# dsau-micro-zed-bank35.net
KiCad netlist of a schematic drawn in Altium Designer
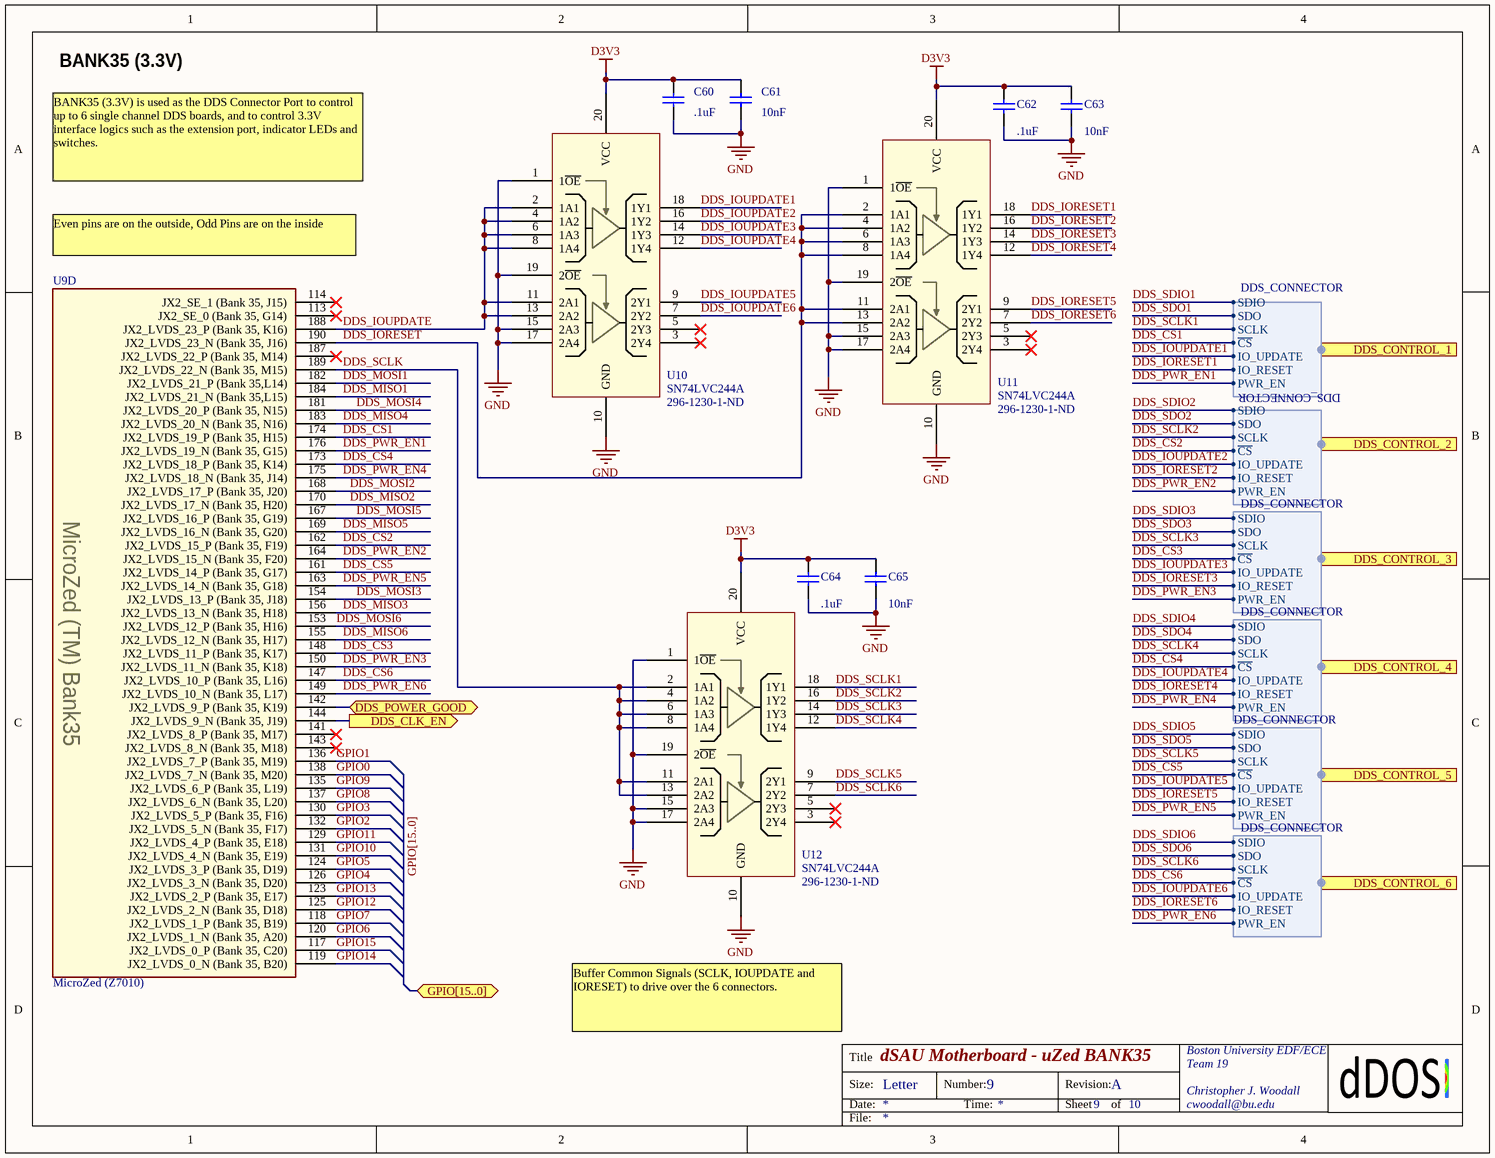
[diagram p0: dsau-micro-zed-bank35.SchDoc]

(export (version "E")
  (design (tool "Eeschema 10.0.6"))
  (components
    (comp (ref "C60")
      (value ".1uF")
      (footprint "CAPC1608L")
      (description "Capacitor")
      (fields
        (field (name "MANUFACTURER") "Yageo")
        (field (name "MANUFACTURER PART NUMBER") "CC0603ZRY5V9BB104")
        (field (name "PUBLISHER") "Altium Limited")
      )
      (libsource (lib "Miscellaneous Devices") (part "Cap"))
    )
    (comp (ref "C61")
      (value "10nF")
      (footprint "CAPC1608L")
      (description "Capacitor")
      (fields
        (field (name "MANUFACTURER") "Kemet")
        (field (name "MANUFACTURER PART NUMBER") "C0603C103K3GACTU")
        (field (name "PUBLISHER") "Altium Limited")
      )
      (libsource (lib "Miscellaneous Devices") (part "Cap"))
    )
    (comp (ref "C62")
      (value ".1uF")
      (footprint "CAPC1608L")
      (description "Capacitor")
      (fields
        (field (name "MANUFACTURER") "Yageo")
        (field (name "MANUFACTURER PART NUMBER") "CC0603ZRY5V9BB104")
        (field (name "PUBLISHER") "Altium Limited")
      )
      (libsource (lib "Miscellaneous Devices") (part "Cap"))
    )
    (comp (ref "C63")
      (value "10nF")
      (footprint "CAPC1608L")
      (description "Capacitor")
      (fields
        (field (name "MANUFACTURER") "Kemet")
        (field (name "MANUFACTURER PART NUMBER") "C0603C103K3GACTU")
        (field (name "PUBLISHER") "Altium Limited")
      )
      (libsource (lib "Miscellaneous Devices") (part "Cap"))
    )
    (comp (ref "C64")
      (value ".1uF")
      (footprint "CAPC1608L")
      (description "Capacitor")
      (fields
        (field (name "MANUFACTURER") "Yageo")
        (field (name "MANUFACTURER PART NUMBER") "CC0603ZRY5V9BB104")
        (field (name "PUBLISHER") "Altium Limited")
      )
      (libsource (lib "Miscellaneous Devices") (part "Cap"))
    )
    (comp (ref "C65")
      (value "10nF")
      (footprint "CAPC1608L")
      (description "Capacitor")
      (fields
        (field (name "MANUFACTURER") "Kemet")
        (field (name "MANUFACTURER PART NUMBER") "C0603C103K3GACTU")
        (field (name "PUBLISHER") "Altium Limited")
      )
      (libsource (lib "Miscellaneous Devices") (part "Cap"))
    )
    (comp (ref "U9")
      (value "MicroZed (Z7010)")
      (footprint "MicroZed_MatingSide")
      (fields
        (field (name "MANUFACTURER") "Avnet")
        (field (name "MANFACTURER PART NUMBER") "AES-Z7MB-7Z010-G")
      )
      (libsource (lib "dsau-motherboard") (part "MicroZed"))
    )
    (comp (ref "U10")
      (value "SN74LVC244A")
      (footprint "TSOP64P640X120-20N")
      (fields
        (field (name "MANUFACTURER") "Texas Instruments")
        (field (name "SUPPLIER PART NUMBER 1") "296-1230-1-ND")
      )
      (libsource (lib "dsau-motherboard") (part "SN74LVC244A"))
    )
    (comp (ref "U11")
      (value "SN74LVC244A")
      (footprint "TSOP64P640X120-20N")
      (fields
        (field (name "MANUFACTURER") "Texas Instruments")
        (field (name "SUPPLIER PART NUMBER 1") "296-1230-1-ND")
      )
      (libsource (lib "dsau-motherboard") (part "SN74LVC244A"))
    )
    (comp (ref "U12")
      (value "SN74LVC244A")
      (footprint "TSOP64P640X120-20N")
      (fields
        (field (name "MANUFACTURER") "Texas Instruments")
        (field (name "SUPPLIER PART NUMBER 1") "296-1230-1-ND")
      )
      (libsource (lib "dsau-motherboard") (part "SN74LVC244A"))
    )
  )
  (nets
    (net (code "3") (name "/DDS_CLK_EN") (class "Default")
      (node (ref "U9") (pin "144") (pinfunction "JX2_LVDS_9_N_(Bank_35,_J19)_144") (pintype "passive"))
    )
    (net (code "5") (name "/DDS_CS1") (class "Default")
      (node (ref "U9") (pin "174") (pinfunction "JX2_LVDS_19_P_(Bank_35,_H15)_174") (pintype "passive"))
    )
    (net (code "6") (name "/DDS_CS2") (class "Default")
      (node (ref "U9") (pin "162") (pinfunction "JX2_LVDS_15_P_(Bank_35,_F19)_162") (pintype "passive"))
    )
    (net (code "7") (name "/DDS_CS3") (class "Default")
      (node (ref "U9") (pin "148") (pinfunction "JX2_LVDS_11_P_(Bank_35,_K17)_148") (pintype "passive"))
    )
    (net (code "8") (name "/DDS_CS4") (class "Default")
      (node (ref "U9") (pin "173") (pinfunction "JX2_LVDS_18_P_(Bank_35,_K14)_173") (pintype "passive"))
    )
    (net (code "9") (name "/DDS_CS5") (class "Default")
      (node (ref "U9") (pin "161") (pinfunction "JX2_LVDS_14_P_(Bank_35,_G17)_161") (pintype "passive"))
    )
    (net (code "10") (name "/DDS_CS6") (class "Default")
      (node (ref "U9") (pin "147") (pinfunction "JX2_LVDS_10_P_(Bank_35,_L16)_147") (pintype "passive"))
    )
    (net (code "11") (name "/DDS_IORESET") (class "Default")
      (node (ref "U11") (pin "11") (pinfunction "2A1_11") (pintype "passive"))
      (node (ref "U11") (pin "13") (pinfunction "2A2_13") (pintype "passive"))
      (node (ref "U11") (pin "2") (pinfunction "1A1_2") (pintype "passive"))
      (node (ref "U11") (pin "4") (pinfunction "1A2_4") (pintype "passive"))
      (node (ref "U11") (pin "6") (pinfunction "1A3_6") (pintype "passive"))
      (node (ref "U11") (pin "8") (pinfunction "1A4_8") (pintype "passive"))
      (node (ref "U9") (pin "190") (pinfunction "JX2_LVDS_23_N_(Bank_35,_J16)_190") (pintype "passive"))
    )
    (net (code "12") (name "/DDS_IORESET1") (class "Default")
      (node (ref "U11") (pin "18") (pinfunction "1Y1_18") (pintype "passive"))
    )
    (net (code "13") (name "/DDS_IORESET2") (class "Default")
      (node (ref "U11") (pin "16") (pinfunction "1Y2_16") (pintype "passive"))
    )
    (net (code "14") (name "/DDS_IORESET3") (class "Default")
      (node (ref "U11") (pin "14") (pinfunction "1Y3_14") (pintype "passive"))
    )
    (net (code "15") (name "/DDS_IORESET4") (class "Default")
      (node (ref "U11") (pin "12") (pinfunction "1Y4_12") (pintype "passive"))
    )
    (net (code "16") (name "/DDS_IORESET5") (class "Default")
      (node (ref "U11") (pin "9") (pinfunction "2Y1_9") (pintype "passive"))
    )
    (net (code "17") (name "/DDS_IORESET6") (class "Default")
      (node (ref "U11") (pin "7") (pinfunction "2Y2_7") (pintype "passive"))
    )
    (net (code "18") (name "/DDS_IOUPDATE") (class "Default")
      (node (ref "U10") (pin "11") (pinfunction "2A1_11") (pintype "passive"))
      (node (ref "U10") (pin "13") (pinfunction "2A2_13") (pintype "passive"))
      (node (ref "U10") (pin "2") (pinfunction "1A1_2") (pintype "passive"))
      (node (ref "U10") (pin "4") (pinfunction "1A2_4") (pintype "passive"))
      (node (ref "U10") (pin "6") (pinfunction "1A3_6") (pintype "passive"))
      (node (ref "U10") (pin "8") (pinfunction "1A4_8") (pintype "passive"))
      (node (ref "U9") (pin "188") (pinfunction "JX2_LVDS_23_P_(Bank_35,_K16)_188") (pintype "passive"))
    )
    (net (code "19") (name "/DDS_IOUPDATE1") (class "Default")
      (node (ref "U10") (pin "18") (pinfunction "1Y1_18") (pintype "passive"))
    )
    (net (code "20") (name "/DDS_IOUPDATE2") (class "Default")
      (node (ref "U10") (pin "16") (pinfunction "1Y2_16") (pintype "passive"))
    )
    (net (code "21") (name "/DDS_IOUPDATE3") (class "Default")
      (node (ref "U10") (pin "14") (pinfunction "1Y3_14") (pintype "passive"))
    )
    (net (code "22") (name "/DDS_IOUPDATE4") (class "Default")
      (node (ref "U10") (pin "12") (pinfunction "1Y4_12") (pintype "passive"))
    )
    (net (code "23") (name "/DDS_IOUPDATE5") (class "Default")
      (node (ref "U10") (pin "9") (pinfunction "2Y1_9") (pintype "passive"))
    )
    (net (code "24") (name "/DDS_IOUPDATE6") (class "Default")
      (node (ref "U10") (pin "7") (pinfunction "2Y2_7") (pintype "passive"))
    )
    (net (code "25") (name "/DDS_MISO1") (class "Default")
      (node (ref "U9") (pin "184") (pinfunction "JX2_LVDS_21_N_(Bank_35,L15)_184") (pintype "passive"))
    )
    (net (code "26") (name "/DDS_MISO2") (class "Default")
      (node (ref "U9") (pin "170") (pinfunction "JX2_LVDS_17_N_(Bank_35,_H20)_170") (pintype "passive"))
    )
    (net (code "27") (name "/DDS_MISO3") (class "Default")
      (node (ref "U9") (pin "156") (pinfunction "JX2_LVDS_13_N_(Bank_35,_H18)_156") (pintype "passive"))
    )
    (net (code "28") (name "/DDS_MISO4") (class "Default")
      (node (ref "U9") (pin "183") (pinfunction "JX2_LVDS_20_N_(Bank_35,_N16)_183") (pintype "passive"))
    )
    (net (code "29") (name "/DDS_MISO5") (class "Default")
      (node (ref "U9") (pin "169") (pinfunction "JX2_LVDS_16_N_(Bank_35,_G20)_169") (pintype "passive"))
    )
    (net (code "30") (name "/DDS_MISO6") (class "Default")
      (node (ref "U9") (pin "155") (pinfunction "JX2_LVDS_12_N_(Bank_35,_H17)_155") (pintype "passive"))
    )
    (net (code "31") (name "/DDS_MOSI1") (class "Default")
      (node (ref "U9") (pin "182") (pinfunction "JX2_LVDS_21_P_(Bank_35,L14)_182") (pintype "passive"))
    )
    (net (code "32") (name "/DDS_MOSI2") (class "Default")
      (node (ref "U9") (pin "168") (pinfunction "JX2_LVDS_17_P_(Bank_35,_J20)_168") (pintype "passive"))
    )
    (net (code "33") (name "/DDS_MOSI3") (class "Default")
      (node (ref "U9") (pin "154") (pinfunction "JX2_LVDS_13_P_(Bank_35,_J18)_154") (pintype "passive"))
    )
    (net (code "34") (name "/DDS_MOSI4") (class "Default")
      (node (ref "U9") (pin "181") (pinfunction "JX2_LVDS_20_P_(Bank_35,_N15)_181") (pintype "passive"))
    )
    (net (code "35") (name "/DDS_MOSI5") (class "Default")
      (node (ref "U9") (pin "167") (pinfunction "JX2_LVDS_16_P_(Bank_35,_G19)_167") (pintype "passive"))
    )
    (net (code "36") (name "/DDS_MOSI6") (class "Default")
      (node (ref "U9") (pin "153") (pinfunction "JX2_LVDS_12_P_(Bank_35,_H16)_153") (pintype "passive"))
    )
    (net (code "37") (name "/DDS_POWER_GOOD") (class "Default")
      (node (ref "U9") (pin "142") (pinfunction "JX2_LVDS_9_P_(Bank_35,_K19)_142") (pintype "passive"))
    )
    (net (code "38") (name "/DDS_PWR_EN1") (class "Default")
      (node (ref "U9") (pin "176") (pinfunction "JX2_LVDS_19_N_(Bank_35,_G15)_176") (pintype "passive"))
    )
    (net (code "39") (name "/DDS_PWR_EN2") (class "Default")
      (node (ref "U9") (pin "164") (pinfunction "JX2_LVDS_15_N_(Bank_35,_F20)_164") (pintype "passive"))
    )
    (net (code "40") (name "/DDS_PWR_EN3") (class "Default")
      (node (ref "U9") (pin "150") (pinfunction "JX2_LVDS_11_N_(Bank_35,_K18)_150") (pintype "passive"))
    )
    (net (code "41") (name "/DDS_PWR_EN4") (class "Default")
      (node (ref "U9") (pin "175") (pinfunction "JX2_LVDS_18_N_(Bank_35,_J14)_175") (pintype "passive"))
    )
    (net (code "42") (name "/DDS_PWR_EN5") (class "Default")
      (node (ref "U9") (pin "163") (pinfunction "JX2_LVDS_14_N_(Bank_35,_G18)_163") (pintype "passive"))
    )
    (net (code "43") (name "/DDS_PWR_EN6") (class "Default")
      (node (ref "U9") (pin "149") (pinfunction "JX2_LVDS_10_N_(Bank_35,_L17)_149") (pintype "passive"))
    )
    (net (code "44") (name "/DDS_SCLK") (class "Default")
      (node (ref "U12") (pin "11") (pinfunction "2A1_11") (pintype "passive"))
      (node (ref "U12") (pin "13") (pinfunction "2A2_13") (pintype "passive"))
      (node (ref "U12") (pin "2") (pinfunction "1A1_2") (pintype "passive"))
      (node (ref "U12") (pin "4") (pinfunction "1A2_4") (pintype "passive"))
      (node (ref "U12") (pin "6") (pinfunction "1A3_6") (pintype "passive"))
      (node (ref "U12") (pin "8") (pinfunction "1A4_8") (pintype "passive"))
      (node (ref "U9") (pin "189") (pinfunction "JX2_LVDS_22_N_(Bank_35,_M15)_189") (pintype "passive"))
    )
    (net (code "45") (name "/DDS_SCLK1") (class "Default")
      (node (ref "U12") (pin "18") (pinfunction "1Y1_18") (pintype "passive"))
    )
    (net (code "46") (name "/DDS_SCLK2") (class "Default")
      (node (ref "U12") (pin "16") (pinfunction "1Y2_16") (pintype "passive"))
    )
    (net (code "47") (name "/DDS_SCLK3") (class "Default")
      (node (ref "U12") (pin "14") (pinfunction "1Y3_14") (pintype "passive"))
    )
    (net (code "48") (name "/DDS_SCLK4") (class "Default")
      (node (ref "U12") (pin "12") (pinfunction "1Y4_12") (pintype "passive"))
    )
    (net (code "49") (name "/DDS_SCLK5") (class "Default")
      (node (ref "U12") (pin "9") (pinfunction "2Y1_9") (pintype "passive"))
    )
    (net (code "50") (name "/DDS_SCLK6") (class "Default")
      (node (ref "U12") (pin "7") (pinfunction "2Y2_7") (pintype "passive"))
    )
    (net (code "63") (name "/GPIO0") (class "Default")
      (node (ref "U9") (pin "138") (pinfunction "JX2_LVDS_7_N_(Bank_35,_M20)_138") (pintype "passive"))
    )
    (net (code "64") (name "/GPIO1") (class "Default")
      (node (ref "U9") (pin "136") (pinfunction "JX2_LVDS_7_P_(Bank_35,_M19)_136") (pintype "passive"))
    )
    (net (code "65") (name "/GPIO2") (class "Default")
      (node (ref "U9") (pin "132") (pinfunction "JX2_LVDS_5_N_(Bank_35,_F17)_132") (pintype "passive"))
    )
    (net (code "66") (name "/GPIO3") (class "Default")
      (node (ref "U9") (pin "130") (pinfunction "JX2_LVDS_5_P_(Bank_35,_F16)_130") (pintype "passive"))
    )
    (net (code "67") (name "/GPIO4") (class "Default")
      (node (ref "U9") (pin "126") (pinfunction "JX2_LVDS_3_N_(Bank_35,_D20)_126") (pintype "passive"))
    )
    (net (code "68") (name "/GPIO5") (class "Default")
      (node (ref "U9") (pin "124") (pinfunction "JX2_LVDS_3_P_(Bank_35,_D19)_124") (pintype "passive"))
    )
    (net (code "69") (name "/GPIO6") (class "Default")
      (node (ref "U9") (pin "120") (pinfunction "JX2_LVDS_1_N_(Bank_35,_A20)_120") (pintype "passive"))
    )
    (net (code "70") (name "/GPIO7") (class "Default")
      (node (ref "U9") (pin "118") (pinfunction "JX2_LVDS_1_P_(Bank_35,_B19)_118") (pintype "passive"))
    )
    (net (code "71") (name "/GPIO8") (class "Default")
      (node (ref "U9") (pin "137") (pinfunction "JX2_LVDS_6_N_(Bank_35,_L20)_137") (pintype "passive"))
    )
    (net (code "72") (name "/GPIO9") (class "Default")
      (node (ref "U9") (pin "135") (pinfunction "JX2_LVDS_6_P_(Bank_35,_L19)_135") (pintype "passive"))
    )
    (net (code "73") (name "/GPIO10") (class "Default")
      (node (ref "U9") (pin "131") (pinfunction "JX2_LVDS_4_N_(Bank_35,_E19)_131") (pintype "passive"))
    )
    (net (code "74") (name "/GPIO11") (class "Default")
      (node (ref "U9") (pin "129") (pinfunction "JX2_LVDS_4_P_(Bank_35,_E18)_129") (pintype "passive"))
    )
    (net (code "75") (name "/GPIO12") (class "Default")
      (node (ref "U9") (pin "125") (pinfunction "JX2_LVDS_2_N_(Bank_35,_D18)_125") (pintype "passive"))
    )
    (net (code "76") (name "/GPIO13") (class "Default")
      (node (ref "U9") (pin "123") (pinfunction "JX2_LVDS_2_P_(Bank_35,_E17)_123") (pintype "passive"))
    )
    (net (code "77") (name "/GPIO14") (class "Default")
      (node (ref "U9") (pin "119") (pinfunction "JX2_LVDS_0_N_(Bank_35,_B20)_119") (pintype "passive"))
    )
    (net (code "78") (name "/GPIO15") (class "Default")
      (node (ref "U9") (pin "117") (pinfunction "JX2_LVDS_0_P_(Bank_35,_C20)_117") (pintype "passive"))
    )
    (net (code "81") (name "D3V3") (class "Default")
      (node (ref "C60") (pin "2") (pinfunction "2_2") (pintype "passive"))
      (node (ref "C61") (pin "1") (pinfunction "1_1") (pintype "passive"))
      (node (ref "C62") (pin "2") (pinfunction "2_2") (pintype "passive"))
      (node (ref "C63") (pin "1") (pinfunction "1_1") (pintype "passive"))
      (node (ref "C64") (pin "2") (pinfunction "2_2") (pintype "passive"))
      (node (ref "C65") (pin "1") (pinfunction "1_1") (pintype "passive"))
      (node (ref "U10") (pin "20") (pinfunction "VCC_20") (pintype "passive"))
      (node (ref "U11") (pin "20") (pinfunction "VCC_20") (pintype "passive"))
      (node (ref "U12") (pin "20") (pinfunction "VCC_20") (pintype "passive"))
    )
    (net (code "82") (name "GND") (class "Default")
      (node (ref "C60") (pin "1") (pinfunction "1_1") (pintype "passive"))
      (node (ref "C61") (pin "2") (pinfunction "2_2") (pintype "passive"))
      (node (ref "C62") (pin "1") (pinfunction "1_1") (pintype "passive"))
      (node (ref "C63") (pin "2") (pinfunction "2_2") (pintype "passive"))
      (node (ref "C64") (pin "1") (pinfunction "1_1") (pintype "passive"))
      (node (ref "C65") (pin "2") (pinfunction "2_2") (pintype "passive"))
      (node (ref "U10") (pin "1") (pinfunction "1~{OE}_1") (pintype "passive"))
      (node (ref "U10") (pin "10") (pinfunction "GND_10") (pintype "passive"))
      (node (ref "U10") (pin "15") (pinfunction "2A3_15") (pintype "passive"))
      (node (ref "U10") (pin "17") (pinfunction "2A4_17") (pintype "passive"))
      (node (ref "U10") (pin "19") (pinfunction "2~{OE}_19") (pintype "passive"))
      (node (ref "U11") (pin "1") (pinfunction "1~{OE}_1") (pintype "passive"))
      (node (ref "U11") (pin "10") (pinfunction "GND_10") (pintype "passive"))
      (node (ref "U11") (pin "15") (pinfunction "2A3_15") (pintype "passive"))
      (node (ref "U11") (pin "17") (pinfunction "2A4_17") (pintype "passive"))
      (node (ref "U11") (pin "19") (pinfunction "2~{OE}_19") (pintype "passive"))
      (node (ref "U12") (pin "1") (pinfunction "1~{OE}_1") (pintype "passive"))
      (node (ref "U12") (pin "10") (pinfunction "GND_10") (pintype "passive"))
      (node (ref "U12") (pin "15") (pinfunction "2A3_15") (pintype "passive"))
      (node (ref "U12") (pin "17") (pinfunction "2A4_17") (pintype "passive"))
      (node (ref "U12") (pin "19") (pinfunction "2~{OE}_19") (pintype "passive"))
    )
    (net (code "83") (name "unconnected-(U9D-JX2_LVDS_8_N_(Bank_35,_M18)-Pad143)") (class "Default")
      (node (ref "U9") (pin "143") (pinfunction "JX2_LVDS_8_N_(Bank_35,_M18)_143") (pintype "passive+no_connect"))
    )
    (net (code "84") (name "unconnected-(U9D-JX2_LVDS_8_P_(Bank_35,_M17)-Pad141)") (class "Default")
      (node (ref "U9") (pin "141") (pinfunction "JX2_LVDS_8_P_(Bank_35,_M17)_141") (pintype "passive+no_connect"))
    )
    (net (code "85") (name "unconnected-(U9D-JX2_LVDS_22_P_(Bank_35,_M14)-Pad187)") (class "Default")
      (node (ref "U9") (pin "187") (pinfunction "JX2_LVDS_22_P_(Bank_35,_M14)_187") (pintype "passive+no_connect"))
    )
    (net (code "86") (name "unconnected-(U9D-JX2_SE_0_(Bank_35,_G14)-Pad113)") (class "Default")
      (node (ref "U9") (pin "113") (pinfunction "JX2_SE_0_(Bank_35,_G14)_113") (pintype "passive+no_connect"))
    )
    (net (code "87") (name "unconnected-(U9D-JX2_SE_1_(Bank_35,_J15)-Pad114)") (class "Default")
      (node (ref "U9") (pin "114") (pinfunction "JX2_SE_1_(Bank_35,_J15)_114") (pintype "passive+no_connect"))
    )
    (net (code "88") (name "unconnected-(U10-2Y3-Pad5)") (class "Default")
      (node (ref "U10") (pin "5") (pinfunction "2Y3_5") (pintype "passive+no_connect"))
    )
    (net (code "89") (name "unconnected-(U10-2Y4-Pad3)") (class "Default")
      (node (ref "U10") (pin "3") (pinfunction "2Y4_3") (pintype "passive+no_connect"))
    )
    (net (code "90") (name "unconnected-(U11-2Y3-Pad5)") (class "Default")
      (node (ref "U11") (pin "5") (pinfunction "2Y3_5") (pintype "passive+no_connect"))
    )
    (net (code "91") (name "unconnected-(U11-2Y4-Pad3)") (class "Default")
      (node (ref "U11") (pin "3") (pinfunction "2Y4_3") (pintype "passive+no_connect"))
    )
    (net (code "92") (name "unconnected-(U12-2Y3-Pad5)") (class "Default")
      (node (ref "U12") (pin "5") (pinfunction "2Y3_5") (pintype "passive+no_connect"))
    )
    (net (code "93") (name "unconnected-(U12-2Y4-Pad3)") (class "Default")
      (node (ref "U12") (pin "3") (pinfunction "2Y4_3") (pintype "passive+no_connect"))
    )
  )
)
